# giraffe_20.net
KiCad netlist of a schematic drawn in EAGLE
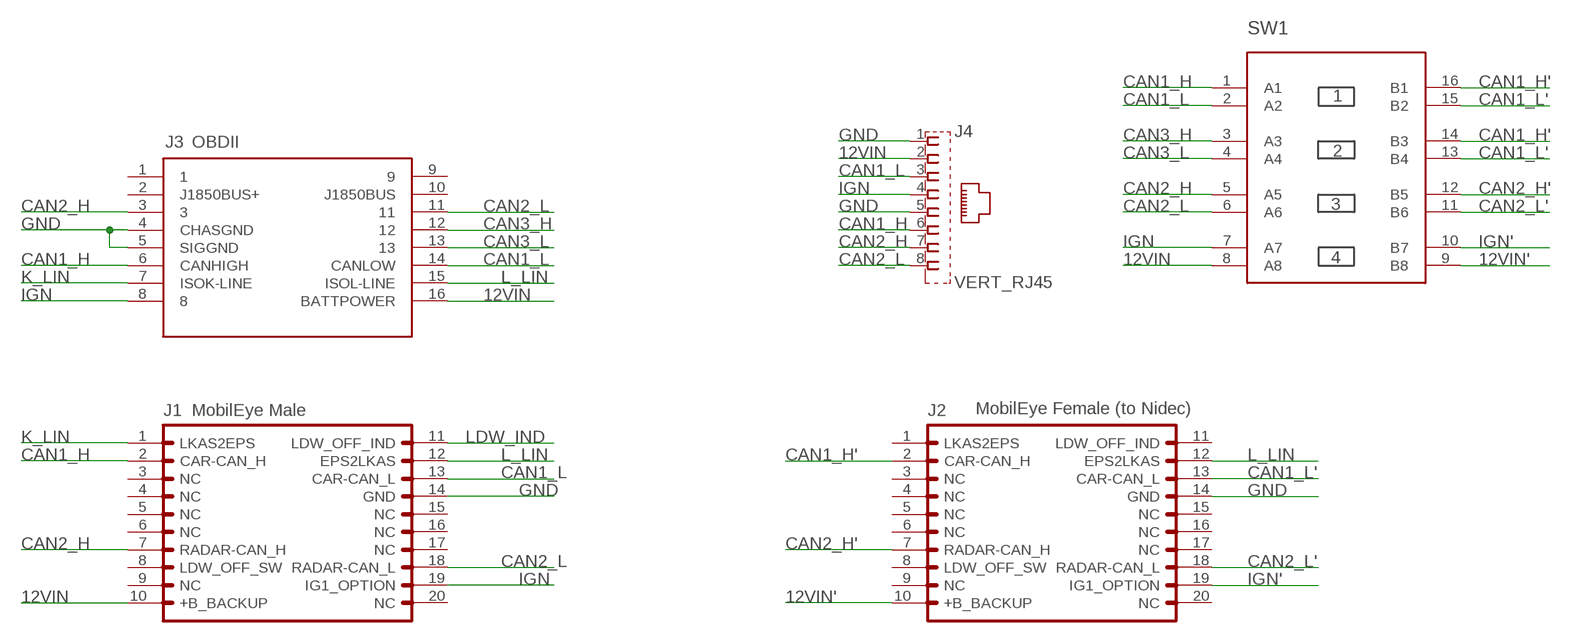
[diagram p0: schematic, sheet 1]

(export (version "E")
  (design (tool "Eeschema 10.0.6"))
  (components
    (comp (ref "J1")
      (value "MOBILEYERAMALE")
      (footprint "eagle-import:2X10(RA)")
      (libsource (lib "eagle-import") (part "MOBILEYERAMALE"))
    )
    (comp (ref "J2")
      (value "MOBILEYEFEMALE")
      (footprint "eagle-import:2X10(JAE_FEMALE)")
      (libsource (lib "eagle-import") (part "MOBILEYEFEMALE"))
    )
    (comp (ref "J3")
      (value "OBDIIFEMALE")
      (footprint "eagle-import:OBDII-FEMALE")
      (libsource (lib "eagle-import") (part "OBDIIFEMALE"))
    )
    (comp (ref "J4")
      (value "VERT_RJ45")
      (footprint "eagle-import:GLX-S-88M")
      (libsource (lib "eagle-import") (part "VERT_RJ45"))
    )
    (comp (ref "SW1")
      (value "4XDPSTSMT")
      (footprint "eagle-import:4-DPST")
      (libsource (lib "eagle-import") (part "4XDPSTSMT"))
    )
  )
  (nets
    (net (code "1") (name "/12VIN") (class "Default")
      (node (ref "J1") (pin "10") (pinfunction "+B_BACKUP_10") (pintype "bidirectional"))
      (node (ref "J3") (pin "16") (pinfunction "BATTPOWER_16") (pintype "bidirectional"))
      (node (ref "J4") (pin "2") (pinfunction "2_2") (pintype "passive"))
      (node (ref "SW1") (pin "8") (pinfunction "A8_8") (pintype "bidirectional"))
    )
    (net (code "2") (name "/12VIN'") (class "Default")
      (node (ref "J2") (pin "10") (pinfunction "+B_BACKUP_10") (pintype "bidirectional"))
      (node (ref "SW1") (pin "9") (pinfunction "B8_9") (pintype "bidirectional"))
    )
    (net (code "3") (name "/CAN1_H") (class "Default")
      (node (ref "J1") (pin "2") (pinfunction "CAR-CAN_H_2") (pintype "bidirectional"))
      (node (ref "J3") (pin "6") (pinfunction "CANHIGH_6") (pintype "bidirectional"))
      (node (ref "J4") (pin "6") (pinfunction "6_6") (pintype "passive"))
      (node (ref "SW1") (pin "1") (pinfunction "A1_1") (pintype "bidirectional"))
    )
    (net (code "4") (name "/CAN1_H'") (class "Default")
      (node (ref "J2") (pin "2") (pinfunction "CAR-CAN_H_2") (pintype "bidirectional"))
      (node (ref "SW1") (pin "14") (pinfunction "B3_14") (pintype "bidirectional"))
      (node (ref "SW1") (pin "16") (pinfunction "B1_16") (pintype "bidirectional"))
    )
    (net (code "5") (name "/CAN1_L") (class "Default")
      (node (ref "J1") (pin "13") (pinfunction "CAR-CAN_L_13") (pintype "bidirectional"))
      (node (ref "J3") (pin "14") (pinfunction "CANLOW_14") (pintype "bidirectional"))
      (node (ref "J4") (pin "3") (pinfunction "3_3") (pintype "passive"))
      (node (ref "SW1") (pin "2") (pinfunction "A2_2") (pintype "bidirectional"))
    )
    (net (code "6") (name "/CAN1_L'") (class "Default")
      (node (ref "J2") (pin "13") (pinfunction "CAR-CAN_L_13") (pintype "bidirectional"))
      (node (ref "SW1") (pin "13") (pinfunction "B4_13") (pintype "bidirectional"))
      (node (ref "SW1") (pin "15") (pinfunction "B2_15") (pintype "bidirectional"))
    )
    (net (code "7") (name "/CAN2_H") (class "Default")
      (node (ref "J1") (pin "7") (pinfunction "RADAR-CAN_H_7") (pintype "bidirectional"))
      (node (ref "J3") (pin "3") (pinfunction "3_3") (pintype "bidirectional"))
      (node (ref "J4") (pin "7") (pinfunction "7_7") (pintype "passive"))
      (node (ref "SW1") (pin "5") (pinfunction "A5_5") (pintype "bidirectional"))
    )
    (net (code "8") (name "/CAN2_H'") (class "Default")
      (node (ref "J2") (pin "7") (pinfunction "RADAR-CAN_H_7") (pintype "bidirectional"))
      (node (ref "SW1") (pin "12") (pinfunction "B5_12") (pintype "bidirectional"))
    )
    (net (code "9") (name "/CAN2_L") (class "Default")
      (node (ref "J1") (pin "18") (pinfunction "RADAR-CAN_L_18") (pintype "bidirectional"))
      (node (ref "J3") (pin "11") (pinfunction "11_11") (pintype "bidirectional"))
      (node (ref "J4") (pin "8") (pinfunction "8_8") (pintype "passive"))
      (node (ref "SW1") (pin "6") (pinfunction "A6_6") (pintype "bidirectional"))
    )
    (net (code "10") (name "/CAN2_L'") (class "Default")
      (node (ref "J2") (pin "18") (pinfunction "RADAR-CAN_L_18") (pintype "bidirectional"))
      (node (ref "SW1") (pin "11") (pinfunction "B6_11") (pintype "bidirectional"))
    )
    (net (code "11") (name "/CAN3_H") (class "Default")
      (node (ref "J3") (pin "12") (pinfunction "12_12") (pintype "bidirectional"))
      (node (ref "SW1") (pin "3") (pinfunction "A3_3") (pintype "bidirectional"))
    )
    (net (code "12") (name "/CAN3_L") (class "Default")
      (node (ref "J3") (pin "13") (pinfunction "13_13") (pintype "bidirectional"))
      (node (ref "SW1") (pin "4") (pinfunction "A4_4") (pintype "bidirectional"))
    )
    (net (code "13") (name "/GND") (class "Default")
      (node (ref "J1") (pin "14") (pinfunction "GND_14") (pintype "bidirectional"))
      (node (ref "J2") (pin "14") (pinfunction "GND_14") (pintype "bidirectional"))
      (node (ref "J3") (pin "4") (pinfunction "CHASGND_4") (pintype "bidirectional"))
      (node (ref "J3") (pin "5") (pinfunction "SIGGND_5") (pintype "bidirectional"))
      (node (ref "J4") (pin "1") (pinfunction "1_1") (pintype "passive"))
      (node (ref "J4") (pin "5") (pinfunction "5_5") (pintype "passive"))
    )
    (net (code "14") (name "/IGN") (class "Default")
      (node (ref "J1") (pin "19") (pinfunction "IG1_OPTION_19") (pintype "bidirectional"))
      (node (ref "J3") (pin "8") (pinfunction "8_8") (pintype "bidirectional"))
      (node (ref "J4") (pin "4") (pinfunction "4_4") (pintype "passive"))
      (node (ref "SW1") (pin "7") (pinfunction "A7_7") (pintype "bidirectional"))
    )
    (net (code "15") (name "/IGN'") (class "Default")
      (node (ref "J2") (pin "19") (pinfunction "IG1_OPTION_19") (pintype "bidirectional"))
      (node (ref "SW1") (pin "10") (pinfunction "B7_10") (pintype "bidirectional"))
    )
    (net (code "16") (name "/K_LIN") (class "Default")
      (node (ref "J1") (pin "1") (pinfunction "LKAS2EPS_1") (pintype "bidirectional"))
      (node (ref "J3") (pin "7") (pinfunction "ISOK-LINE_7") (pintype "bidirectional"))
    )
    (net (code "17") (name "/LDW_IND") (class "Default")
      (node (ref "J1") (pin "11") (pinfunction "LDW_OFF_IND_11") (pintype "bidirectional"))
    )
    (net (code "18") (name "/L_LIN") (class "Default")
      (node (ref "J1") (pin "12") (pinfunction "EPS2LKAS_12") (pintype "bidirectional"))
      (node (ref "J2") (pin "12") (pinfunction "EPS2LKAS_12") (pintype "bidirectional"))
      (node (ref "J3") (pin "15") (pinfunction "ISOL-LINE_15") (pintype "bidirectional"))
    )
    (net (code "19") (name "unconnected-(J1-LDW_OFF_SW-Pad8)") (class "Default")
      (node (ref "J1") (pin "8") (pinfunction "LDW_OFF_SW_8") (pintype "bidirectional"))
    )
    (net (code "20") (name "unconnected-(J1-NC-Pad3)") (class "Default")
      (node (ref "J1") (pin "3") (pinfunction "NC_3") (pintype "bidirectional"))
    )
    (net (code "21") (name "unconnected-(J1-NC-Pad4)") (class "Default")
      (node (ref "J1") (pin "4") (pinfunction "NC_4") (pintype "bidirectional"))
    )
    (net (code "22") (name "unconnected-(J1-NC-Pad5)") (class "Default")
      (node (ref "J1") (pin "5") (pinfunction "NC_5") (pintype "bidirectional"))
    )
    (net (code "23") (name "unconnected-(J1-NC-Pad6)") (class "Default")
      (node (ref "J1") (pin "6") (pinfunction "NC_6") (pintype "bidirectional"))
    )
    (net (code "24") (name "unconnected-(J1-NC-Pad9)") (class "Default")
      (node (ref "J1") (pin "9") (pinfunction "NC_9") (pintype "bidirectional"))
    )
    (net (code "25") (name "unconnected-(J1-NC-Pad15)") (class "Default")
      (node (ref "J1") (pin "15") (pinfunction "NC_15") (pintype "bidirectional"))
    )
    (net (code "26") (name "unconnected-(J1-NC-Pad16)") (class "Default")
      (node (ref "J1") (pin "16") (pinfunction "NC_16") (pintype "bidirectional"))
    )
    (net (code "27") (name "unconnected-(J1-NC-Pad17)") (class "Default")
      (node (ref "J1") (pin "17") (pinfunction "NC_17") (pintype "bidirectional"))
    )
    (net (code "28") (name "unconnected-(J1-NC-Pad20)") (class "Default")
      (node (ref "J1") (pin "20") (pinfunction "NC_20") (pintype "bidirectional"))
    )
    (net (code "29") (name "unconnected-(J2-LDW_OFF_IND-Pad11)") (class "Default")
      (node (ref "J2") (pin "11") (pinfunction "LDW_OFF_IND_11") (pintype "bidirectional"))
    )
    (net (code "30") (name "unconnected-(J2-LDW_OFF_SW-Pad8)") (class "Default")
      (node (ref "J2") (pin "8") (pinfunction "LDW_OFF_SW_8") (pintype "bidirectional"))
    )
    (net (code "31") (name "unconnected-(J2-LKAS2EPS-Pad1)") (class "Default")
      (node (ref "J2") (pin "1") (pinfunction "LKAS2EPS_1") (pintype "bidirectional"))
    )
    (net (code "32") (name "unconnected-(J2-NC-Pad3)") (class "Default")
      (node (ref "J2") (pin "3") (pinfunction "NC_3") (pintype "bidirectional"))
    )
    (net (code "33") (name "unconnected-(J2-NC-Pad4)") (class "Default")
      (node (ref "J2") (pin "4") (pinfunction "NC_4") (pintype "bidirectional"))
    )
    (net (code "34") (name "unconnected-(J2-NC-Pad5)") (class "Default")
      (node (ref "J2") (pin "5") (pinfunction "NC_5") (pintype "bidirectional"))
    )
    (net (code "35") (name "unconnected-(J2-NC-Pad6)") (class "Default")
      (node (ref "J2") (pin "6") (pinfunction "NC_6") (pintype "bidirectional"))
    )
    (net (code "36") (name "unconnected-(J2-NC-Pad9)") (class "Default")
      (node (ref "J2") (pin "9") (pinfunction "NC_9") (pintype "bidirectional"))
    )
    (net (code "37") (name "unconnected-(J2-NC-Pad15)") (class "Default")
      (node (ref "J2") (pin "15") (pinfunction "NC_15") (pintype "bidirectional"))
    )
    (net (code "38") (name "unconnected-(J2-NC-Pad16)") (class "Default")
      (node (ref "J2") (pin "16") (pinfunction "NC_16") (pintype "bidirectional"))
    )
    (net (code "39") (name "unconnected-(J2-NC-Pad17)") (class "Default")
      (node (ref "J2") (pin "17") (pinfunction "NC_17") (pintype "bidirectional"))
    )
    (net (code "40") (name "unconnected-(J2-NC-Pad20)") (class "Default")
      (node (ref "J2") (pin "20") (pinfunction "NC_20") (pintype "bidirectional"))
    )
    (net (code "41") (name "unconnected-(J3-J1850BUS+-Pad2)") (class "Default")
      (node (ref "J3") (pin "2") (pinfunction "J1850BUS+_2") (pintype "bidirectional"))
    )
    (net (code "42") (name "unconnected-(J3-J1850BUS-Pad10)") (class "Default")
      (node (ref "J3") (pin "10") (pinfunction "J1850BUS_10") (pintype "bidirectional"))
    )
    (net (code "43") (name "unconnected-(J3-Pad1)") (class "Default")
      (node (ref "J3") (pin "1") (pinfunction "1_1") (pintype "bidirectional"))
    )
    (net (code "44") (name "unconnected-(J3-Pad9)") (class "Default")
      (node (ref "J3") (pin "9") (pinfunction "9_9") (pintype "bidirectional"))
    )
  )
)
